# LoadCkt.net
KiCad netlist of a schematic drawn in EAGLE
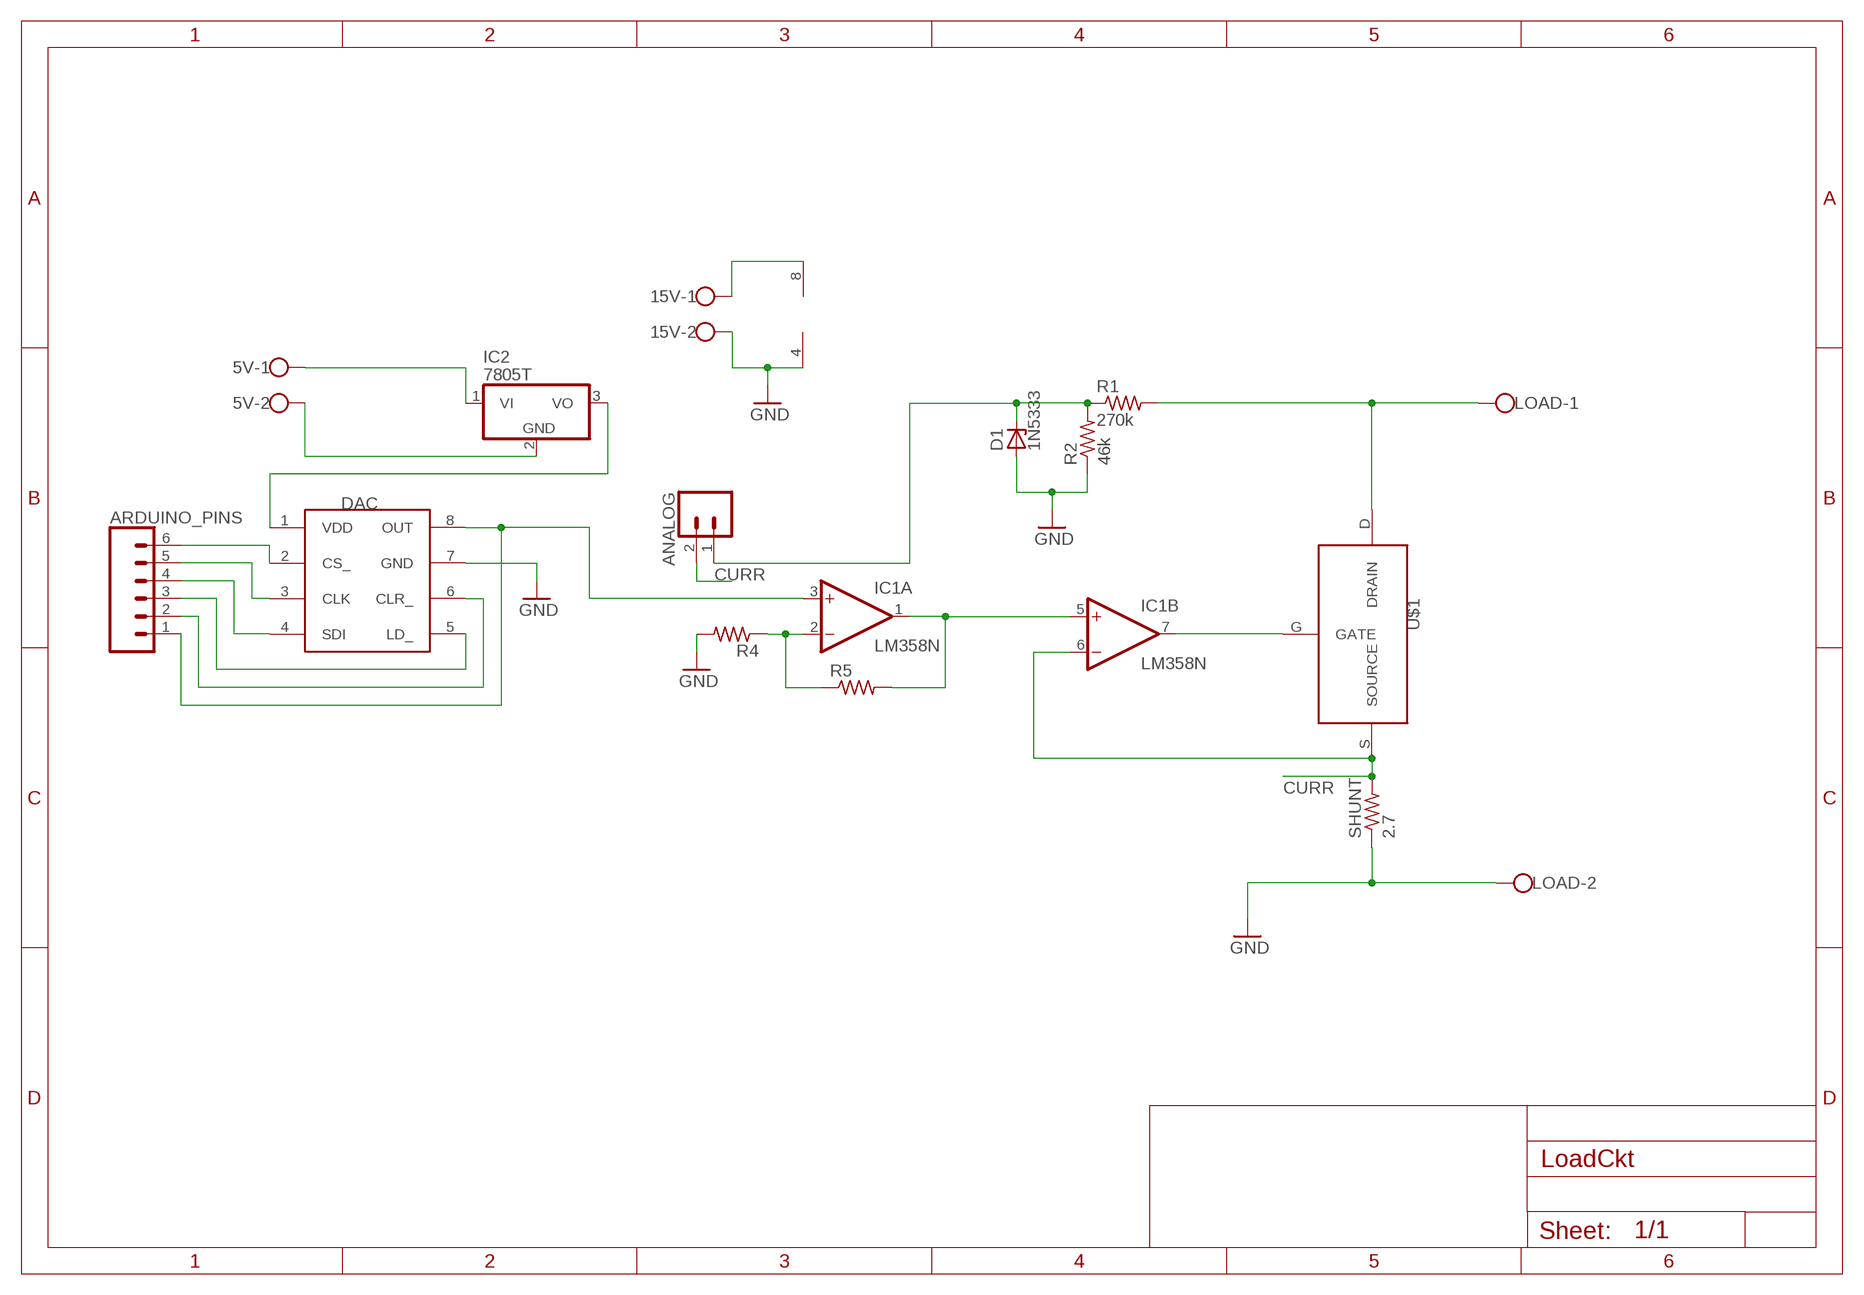
[diagram p0: schematic, sheet 1]

(export (version "E")
  (design (tool "Eeschema 10.0.6"))
  (components
    (comp (ref "5V")
      (value "W237-102")
      (footprint "eagle-import:W237-102")
      (fields (field (name "MPN") "237-102"))
      (libsource (lib "eagle-import") (part "W237-102"))
    )
    (comp (ref "15V")
      (value "W237-102")
      (footprint "eagle-import:W237-102")
      (fields (field (name "MPN") "237-102"))
      (libsource (lib "eagle-import") (part "W237-102"))
    )
    (comp (ref "ANALOG")
      (value "CONN_02")
      (footprint "eagle-import:1X02")
      (libsource (lib "eagle-import") (part "CONN_02"))
    )
    (comp (ref "ARDUINO_PINS")
      (value "CONN_06SILK_FEMALE_PTH")
      (footprint "eagle-import:1X06")
      (libsource (lib "eagle-import") (part "CONN_06SILK_FEMALE_PTH"))
    )
    (comp (ref "D1")
      (value "1N5333")
      (footprint "eagle-import:C1702-15")
      (libsource (lib "eagle-import") (part "1N5333"))
    )
    (comp (ref "DAC")
      (value "DAC7611DIP")
      (footprint "eagle-import:DP-04")
      (libsource (lib "eagle-import") (part "DAC7611DIP"))
    )
    (comp (ref "IC1")
      (value "LM358N")
      (footprint "eagle-import:DIL08")
      (libsource (lib "eagle-import") (part "LM358N"))
    )
    (comp (ref "IC2")
      (value "7805T")
      (footprint "eagle-import:TO220H")
      (libsource (lib "eagle-import") (part "78T05"))
    )
    (comp (ref "LOAD")
      (value "W237-102")
      (footprint "eagle-import:W237-102")
      (fields (field (name "MPN") "237-102"))
      (libsource (lib "eagle-import") (part "W237-102"))
    )
    (comp (ref "R1")
      (value "270k")
      (footprint "eagle-import:0204_7")
      (libsource (lib "eagle-import") (part "R-US_0204/7"))
    )
    (comp (ref "R2")
      (value "46k")
      (footprint "eagle-import:0204_7")
      (libsource (lib "eagle-import") (part "R-US_0204/7"))
    )
    (comp (ref "R4")
      (value "R-US_0204/7")
      (footprint "eagle-import:0204_7")
      (libsource (lib "eagle-import") (part "R-US_0204/7"))
    )
    (comp (ref "R5")
      (value "R-US_0204/7")
      (footprint "eagle-import:0204_7")
      (libsource (lib "eagle-import") (part "R-US_0204/7"))
    )
    (comp (ref "SHUNT")
      (value "2.7")
      (footprint "eagle-import:0204_7")
      (libsource (lib "eagle-import") (part "R-US_0204/7"))
    )
    (comp (ref "U$1")
      (value "IRFP4468")
      (footprint "eagle-import:TO-247AD-H")
      (libsource (lib "eagle-import") (part "IRFP4468"))
    )
  )
  (nets
    (net (code "1") (name "/CURR") (class "Default")
      (node (ref "ANALOG") (pin "2") (pinfunction "2_2") (pintype "passive"))
      (node (ref "IC1") (pin "6") (pinfunction "-IN_6") (pintype "input"))
      (node (ref "SHUNT") (pin "2") (pinfunction "2_2") (pintype "passive"))
      (node (ref "U$1") (pin "S") (pinfunction "SOURCE_S") (pintype "bidirectional"))
    )
    (net (code "2") (name "GND") (class "Default")
      (node (ref "15V") (pin "2") (pinfunction "KL_2") (pintype "passive"))
      (node (ref "D1") (pin "A") (pinfunction "A_A") (pintype "passive"))
      (node (ref "DAC") (pin "7") (pinfunction "GND_7") (pintype "bidirectional"))
      (node (ref "IC1") (pin "4") (pinfunction "V-_4") (pintype "power_in"))
      (node (ref "LOAD") (pin "2") (pinfunction "KL_2") (pintype "passive"))
      (node (ref "R2") (pin "1") (pinfunction "1_1") (pintype "passive"))
      (node (ref "R4") (pin "2") (pinfunction "2_2") (pintype "passive"))
      (node (ref "SHUNT") (pin "1") (pinfunction "1_1") (pintype "passive"))
    )
    (net (code "3") (name "Net-(5VA-KL)") (class "Default")
      (node (ref "5V") (pin "1") (pinfunction "KL_1") (pintype "passive"))
      (node (ref "IC2") (pin "1") (pinfunction "VI_1") (pintype "input"))
    )
    (net (code "4") (name "Net-(5VB-KL)") (class "Default")
      (node (ref "5V") (pin "2") (pinfunction "KL_2") (pintype "passive"))
      (node (ref "IC2") (pin "2") (pinfunction "GND_2") (pintype "passive"))
    )
    (net (code "5") (name "Net-(15VA-KL)") (class "Default")
      (node (ref "15V") (pin "1") (pinfunction "KL_1") (pintype "passive"))
      (node (ref "IC1") (pin "8") (pinfunction "V+_8") (pintype "power_in"))
    )
    (net (code "6") (name "Net-(ANALOG-Pad1)") (class "Default")
      (node (ref "ANALOG") (pin "1") (pinfunction "1_1") (pintype "passive"))
      (node (ref "D1") (pin "C") (pinfunction "C_C") (pintype "passive"))
      (node (ref "R1") (pin "1") (pinfunction "1_1") (pintype "passive"))
      (node (ref "R2") (pin "2") (pinfunction "2_2") (pintype "passive"))
    )
    (net (code "7") (name "Net-(DAC-CLK)") (class "Default")
      (node (ref "ARDUINO_PINS") (pin "5") (pinfunction "5_5") (pintype "passive"))
      (node (ref "DAC") (pin "3") (pinfunction "CLK_3") (pintype "bidirectional"))
    )
    (net (code "8") (name "Net-(DAC-CLR_)") (class "Default")
      (node (ref "ARDUINO_PINS") (pin "2") (pinfunction "2_2") (pintype "passive"))
      (node (ref "DAC") (pin "6") (pinfunction "CLR__6") (pintype "bidirectional"))
    )
    (net (code "9") (name "Net-(DAC-CS_)") (class "Default")
      (node (ref "ARDUINO_PINS") (pin "6") (pinfunction "6_6") (pintype "passive"))
      (node (ref "DAC") (pin "2") (pinfunction "CS__2") (pintype "bidirectional"))
    )
    (net (code "10") (name "Net-(DAC-LD_)") (class "Default")
      (node (ref "ARDUINO_PINS") (pin "3") (pinfunction "3_3") (pintype "passive"))
      (node (ref "DAC") (pin "5") (pinfunction "LD__5") (pintype "bidirectional"))
    )
    (net (code "11") (name "Net-(DAC-OUT)") (class "Default")
      (node (ref "ARDUINO_PINS") (pin "1") (pinfunction "1_1") (pintype "passive"))
      (node (ref "DAC") (pin "8") (pinfunction "OUT_8") (pintype "output"))
      (node (ref "IC1") (pin "3") (pinfunction "+IN_3") (pintype "input"))
    )
    (net (code "12") (name "Net-(DAC-SDI)") (class "Default")
      (node (ref "ARDUINO_PINS") (pin "4") (pinfunction "4_4") (pintype "passive"))
      (node (ref "DAC") (pin "4") (pinfunction "SDI_4") (pintype "bidirectional"))
    )
    (net (code "13") (name "Net-(DAC-VDD)") (class "Default")
      (node (ref "DAC") (pin "1") (pinfunction "VDD_1") (pintype "power_in"))
      (node (ref "IC2") (pin "3") (pinfunction "VO_3") (pintype "passive"))
    )
    (net (code "14") (name "Net-(IC1A--IN)") (class "Default")
      (node (ref "IC1") (pin "2") (pinfunction "-IN_2") (pintype "input"))
      (node (ref "R4") (pin "1") (pinfunction "1_1") (pintype "passive"))
      (node (ref "R5") (pin "1") (pinfunction "1_1") (pintype "passive"))
    )
    (net (code "15") (name "Net-(IC1A-OUT)") (class "Default")
      (node (ref "IC1") (pin "1") (pinfunction "OUT_1") (pintype "output"))
      (node (ref "IC1") (pin "5") (pinfunction "+IN_5") (pintype "input"))
      (node (ref "R5") (pin "2") (pinfunction "2_2") (pintype "passive"))
    )
    (net (code "16") (name "Net-(IC1B-OUT)") (class "Default")
      (node (ref "IC1") (pin "7") (pinfunction "OUT_7") (pintype "output"))
      (node (ref "U$1") (pin "G") (pinfunction "GATE_G") (pintype "bidirectional"))
    )
    (net (code "17") (name "Net-(LOADA-KL)") (class "Default")
      (node (ref "LOAD") (pin "1") (pinfunction "KL_1") (pintype "passive"))
      (node (ref "R1") (pin "2") (pinfunction "2_2") (pintype "passive"))
      (node (ref "U$1") (pin "D") (pinfunction "DRAIN_D") (pintype "bidirectional"))
    )
  )
)
